# ACS_Temperature_Sensor.net
KiCad netlist of a schematic drawn in EasyEDA Pro
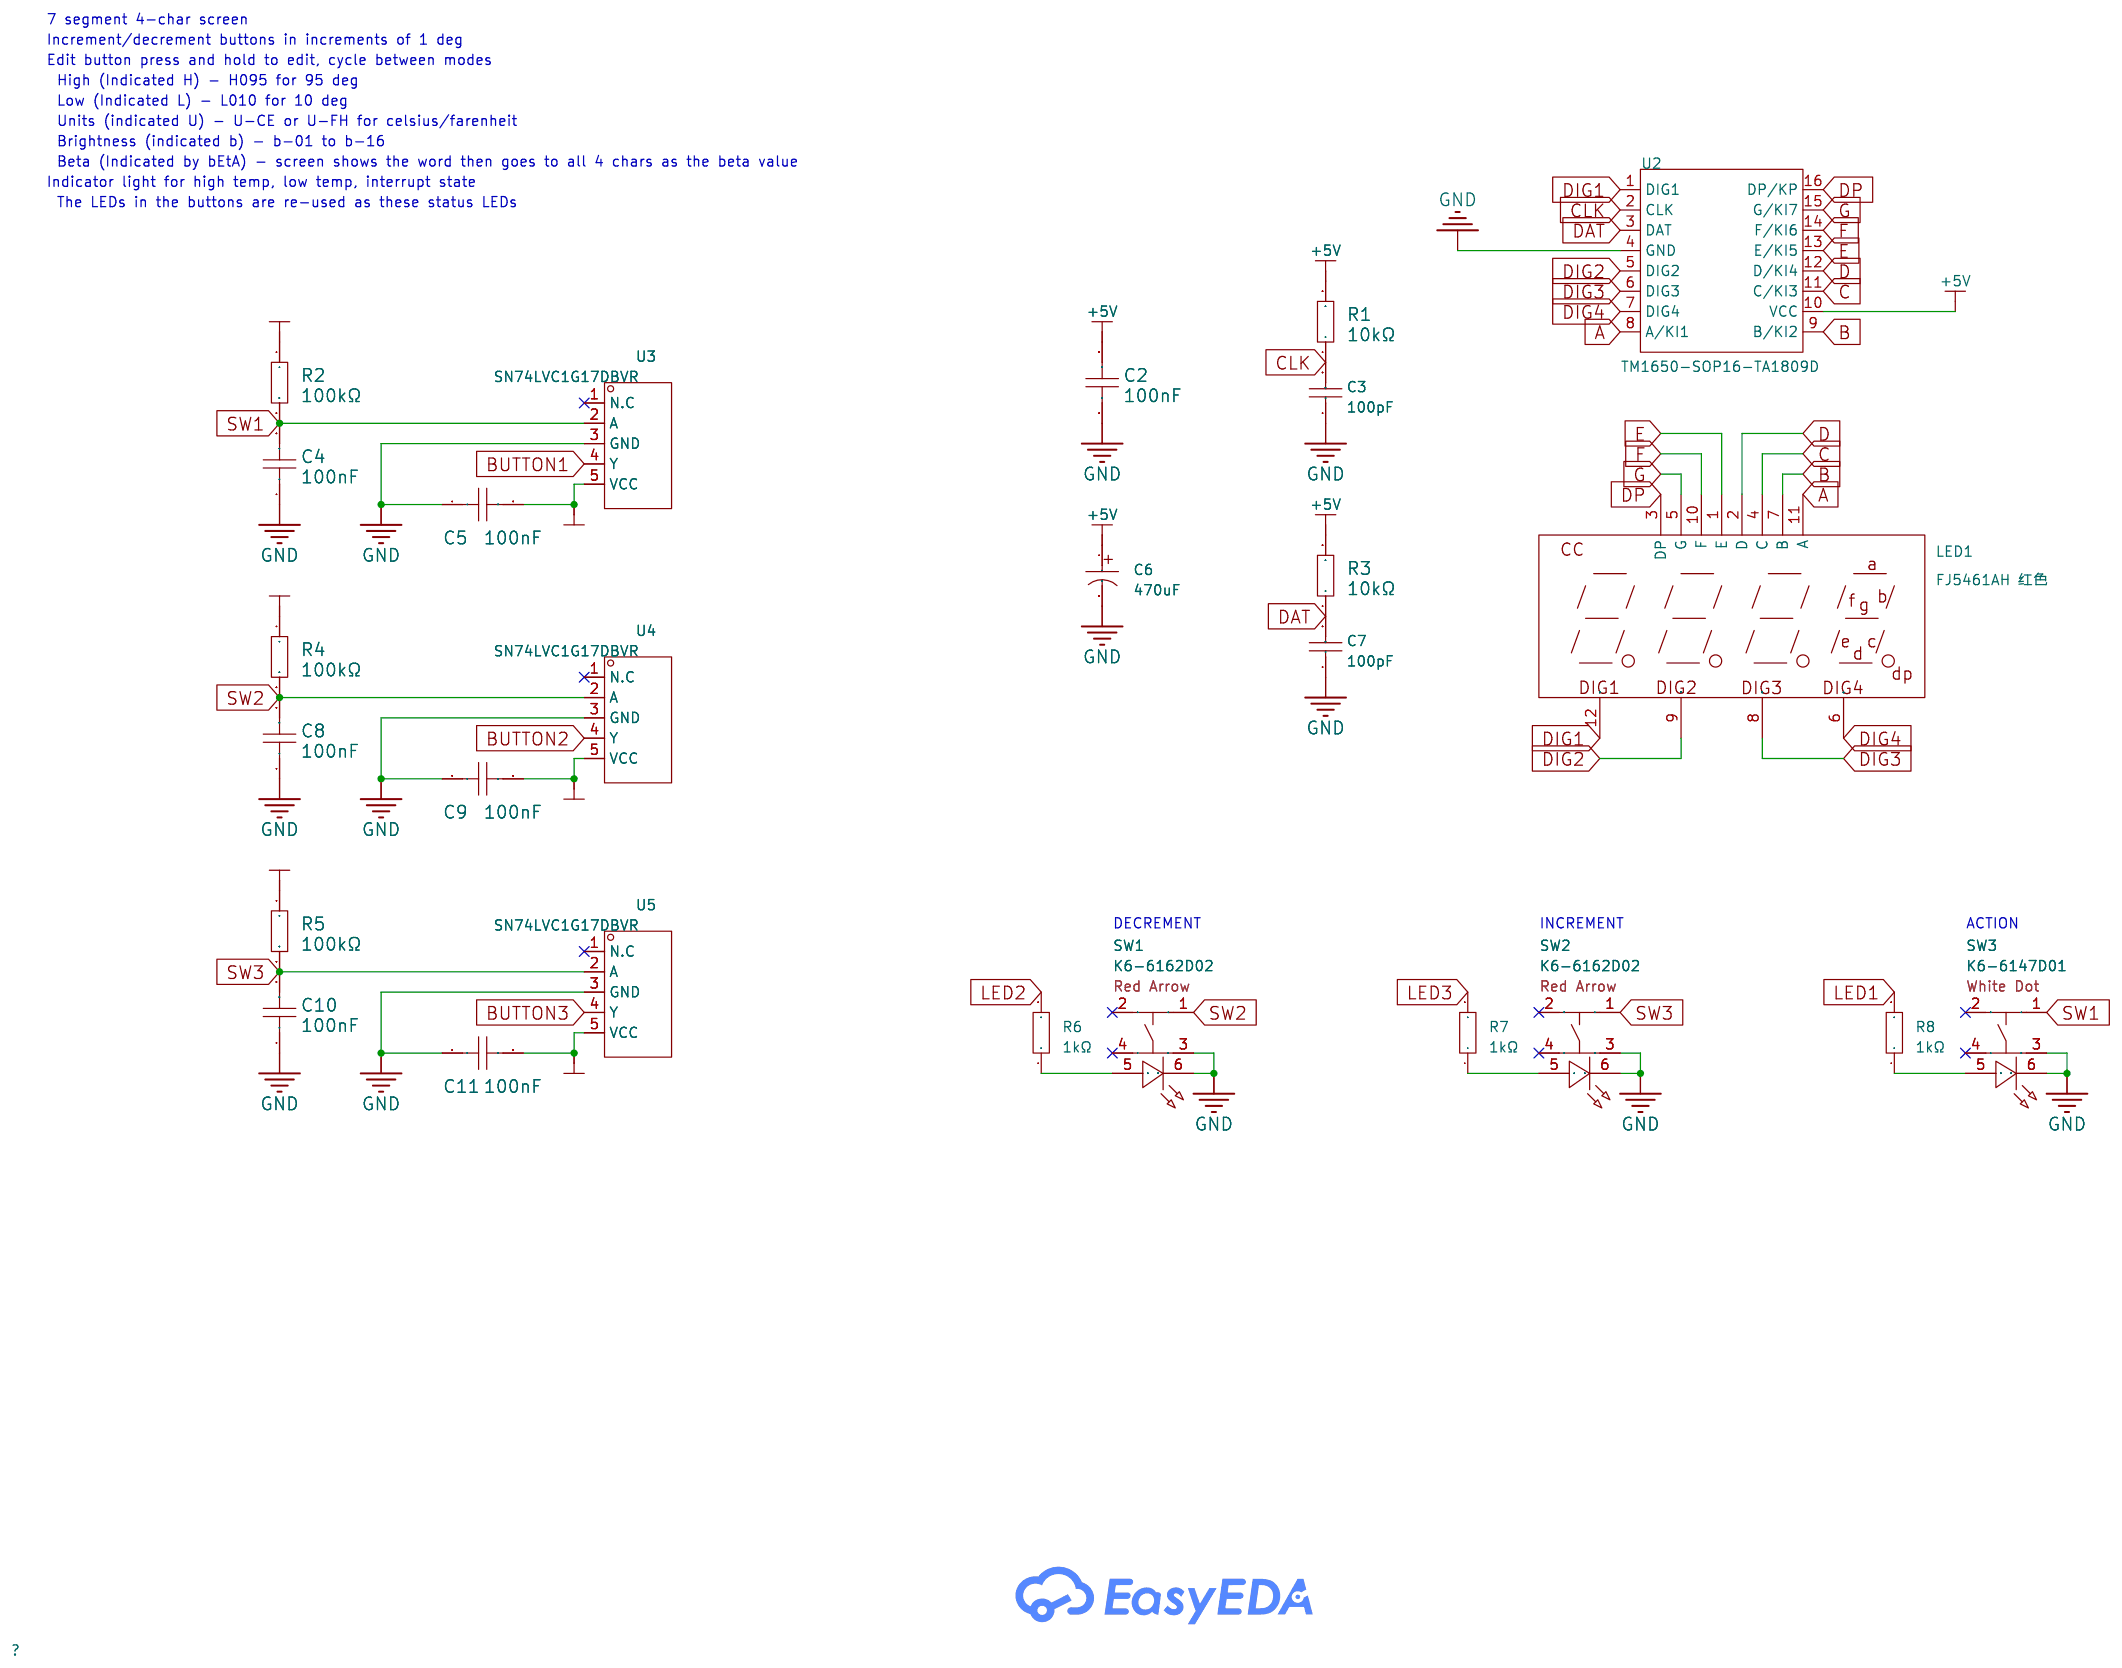
[diagram p0: User Interface]
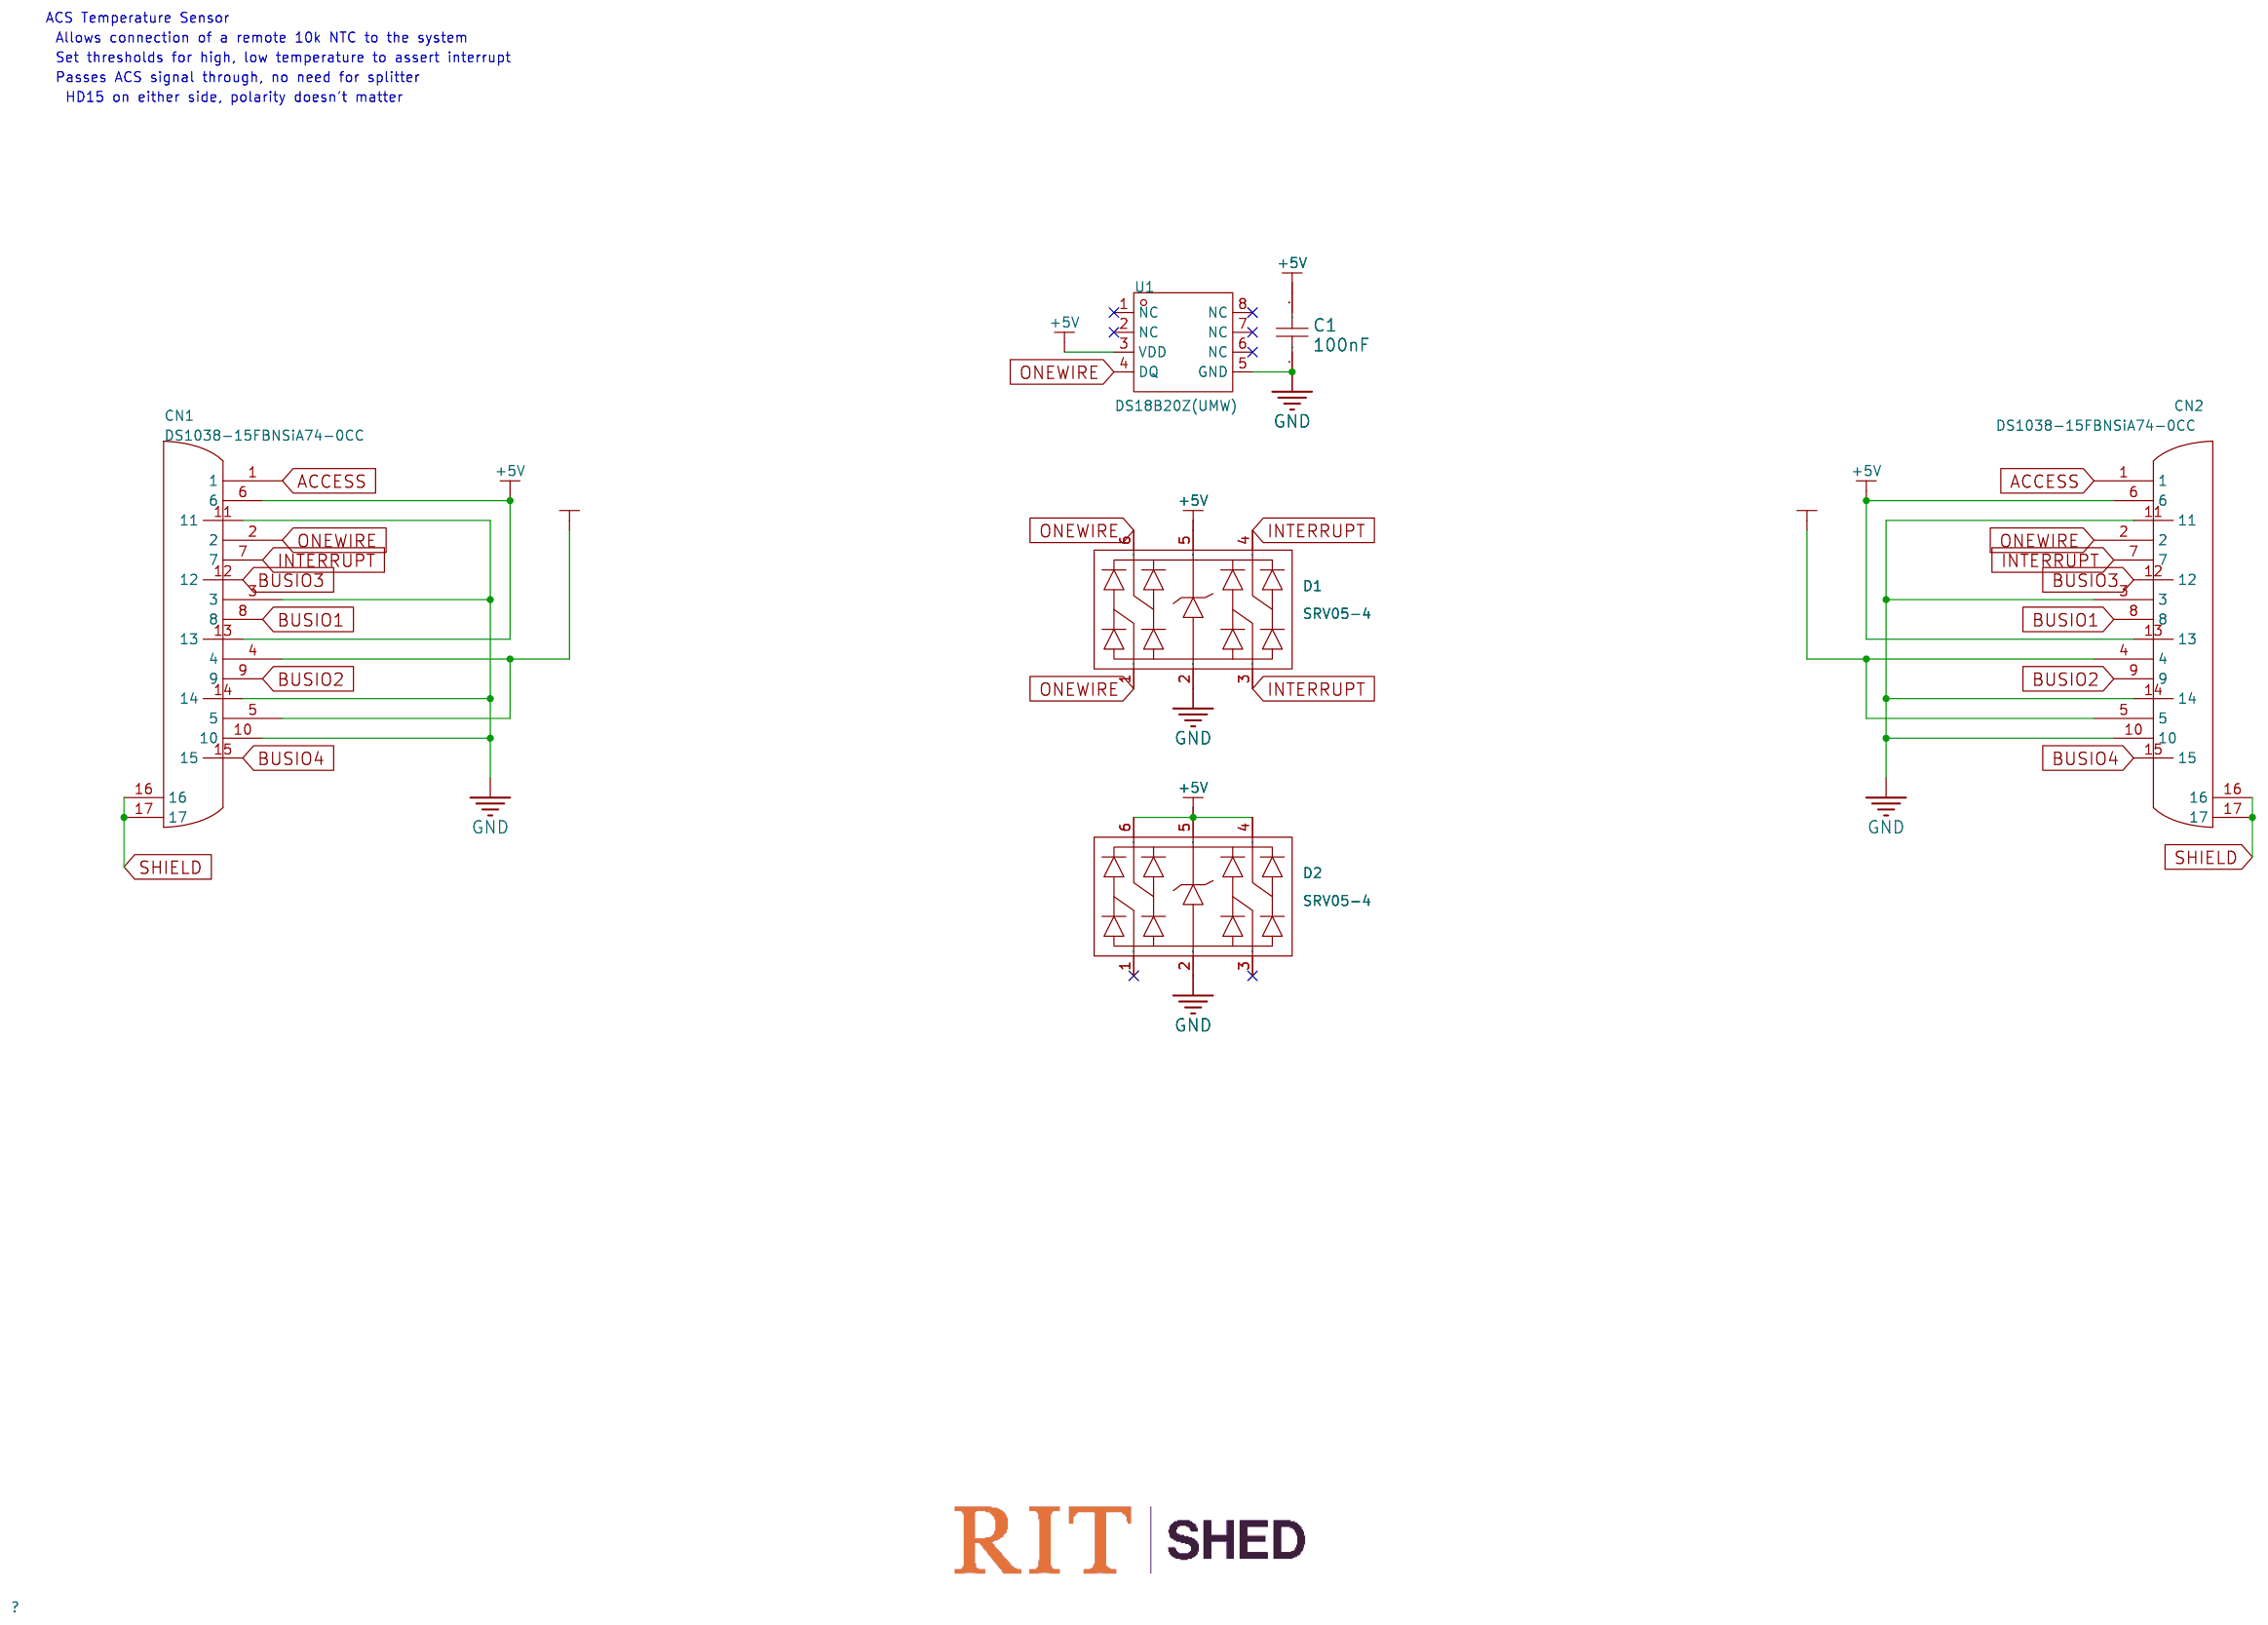
[diagram p1: ACS Interface]
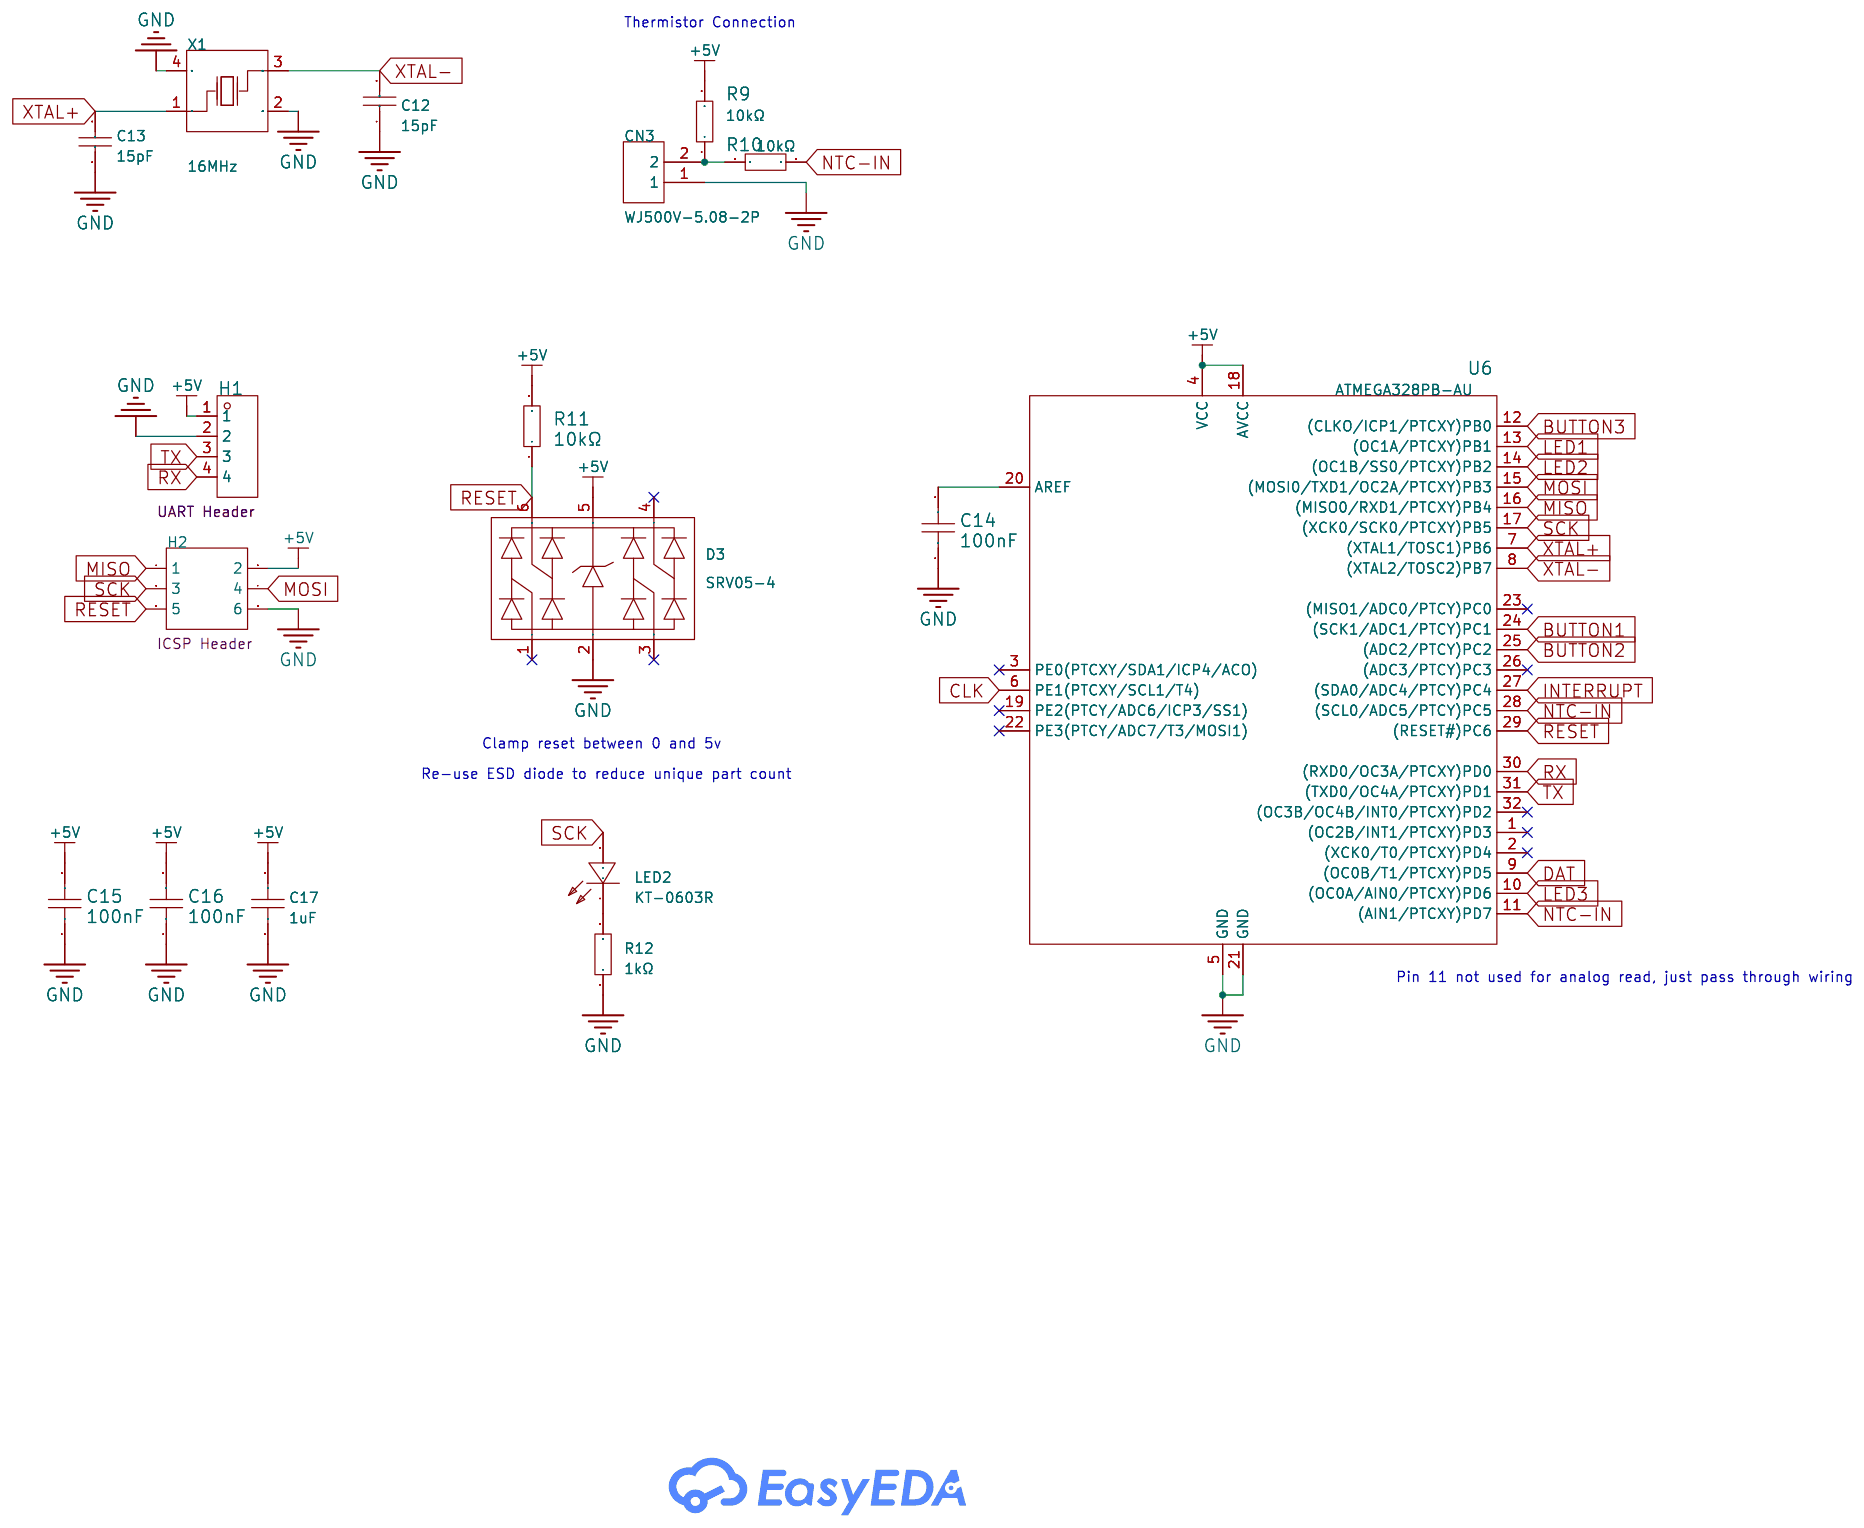
[diagram p2: Microcontroller]

(export (version "E")
  (design (tool "Eeschema 10.0.6"))
  (components
    (comp (ref "C2")
      (value "100nF")
      (footprint "easyedapro:C0603")
      (description "Capacitance:100nF Tolerance:±10% Tolerance:±10% Voltage Rating:50V Temperature Coefficient:X7R")
      (fields
        (field (name "Manufacturer Part") "CC0603KRX7R9BB104")
        (field (name "Manufacturer") "YAGEO(国巨)")
      )
      (libsource (lib "easyedapro") (part "CC0603KRX7R9BB104"))
    )
    (comp (ref "C3")
      (value "100pF")
      (footprint "easyedapro:C0603")
      (description "Capacitance:100pF Tolerance:±5% Tolerance:±5% Voltage Rating:50V Temperature Coefficient:C0G")
      (fields
        (field (name "Manufacturer Part") "CL10C101JB8NNNC")
        (field (name "Manufacturer") "SAMSUNG(三星)")
      )
      (libsource (lib "easyedapro") (part "CL10C101JB8NNNC"))
    )
    (comp (ref "C4")
      (value "100nF")
      (footprint "easyedapro:C0603")
      (description "Capacitance:100nF Tolerance:±10% Tolerance:±10% Voltage Rating:50V Temperature Coefficient:X7R")
      (fields
        (field (name "Manufacturer Part") "CC0603KRX7R9BB104")
        (field (name "Manufacturer") "YAGEO(国巨)")
      )
      (libsource (lib "easyedapro") (part "CC0603KRX7R9BB104"))
    )
    (comp (ref "C5")
      (value "100nF")
      (footprint "easyedapro:C0603")
      (description "Capacitance:100nF Tolerance:±10% Tolerance:±10% Voltage Rating:50V Temperature Coefficient:X7R")
      (fields
        (field (name "Manufacturer Part") "CC0603KRX7R9BB104")
        (field (name "Manufacturer") "YAGEO(国巨)")
      )
      (libsource (lib "easyedapro") (part "CC0603KRX7R9BB104"))
    )
    (comp (ref "C6")
      (value "470uF")
      (footprint "easyedapro:CAP-TH_BD8.0-P3.50-D0.6-FD")
      (fields
        (field (name "Manufacturer Part") "ZF477M016F07RR0VH4FPV")
        (field (name "Manufacturer") "Chengx(承兴)")
      )
      (libsource (lib "easyedapro") (part "470uF 16V 8*7Black high frequency"))
    )
    (comp (ref "C7")
      (value "100pF")
      (footprint "easyedapro:C0603")
      (description "Capacitance:100pF Tolerance:±5% Tolerance:±5% Voltage Rating:50V Temperature Coefficient:C0G")
      (fields
        (field (name "Manufacturer Part") "CL10C101JB8NNNC")
        (field (name "Manufacturer") "SAMSUNG(三星)")
      )
      (libsource (lib "easyedapro") (part "CL10C101JB8NNNC"))
    )
    (comp (ref "C8")
      (value "100nF")
      (footprint "easyedapro:C0603")
      (description "Capacitance:100nF Tolerance:±10% Tolerance:±10% Voltage Rating:50V Temperature Coefficient:X7R")
      (fields
        (field (name "Manufacturer Part") "CC0603KRX7R9BB104")
        (field (name "Manufacturer") "YAGEO(国巨)")
      )
      (libsource (lib "easyedapro") (part "CC0603KRX7R9BB104"))
    )
    (comp (ref "C9")
      (value "100nF")
      (footprint "easyedapro:C0603")
      (description "Capacitance:100nF Tolerance:±10% Tolerance:±10% Voltage Rating:50V Temperature Coefficient:X7R")
      (fields
        (field (name "Manufacturer Part") "CC0603KRX7R9BB104")
        (field (name "Manufacturer") "YAGEO(国巨)")
      )
      (libsource (lib "easyedapro") (part "CC0603KRX7R9BB104"))
    )
    (comp (ref "C10")
      (value "100nF")
      (footprint "easyedapro:C0603")
      (description "Capacitance:100nF Tolerance:±10% Tolerance:±10% Voltage Rating:50V Temperature Coefficient:X7R")
      (fields
        (field (name "Manufacturer Part") "CC0603KRX7R9BB104")
        (field (name "Manufacturer") "YAGEO(国巨)")
      )
      (libsource (lib "easyedapro") (part "CC0603KRX7R9BB104"))
    )
    (comp (ref "C11")
      (value "100nF")
      (footprint "easyedapro:C0603")
      (description "Capacitance:100nF Tolerance:±10% Tolerance:±10% Voltage Rating:50V Temperature Coefficient:X7R")
      (fields
        (field (name "Manufacturer Part") "CC0603KRX7R9BB104")
        (field (name "Manufacturer") "YAGEO(国巨)")
      )
      (libsource (lib "easyedapro") (part "CC0603KRX7R9BB104"))
    )
    (comp (ref "LED1")
      (value "FJ5461AH 红色")
      (footprint "easyedapro:LED-SEG-TH_FJ5461AH")
      (fields (field (name "Manufacturer") "志浩"))
      (libsource (lib "easyedapro") (part "FJ5461AH red"))
    )
    (comp (ref "R1")
      (value "10kΩ")
      (footprint "easyedapro:R0603")
      (fields
        (field (name "Manufacturer Part") "0603WAF1002T5E")
        (field (name "Manufacturer") "UNI-ROYAL(厚声)")
      )
      (libsource (lib "easyedapro") (part "0603WAF1002T5E"))
    )
    (comp (ref "R2")
      (value "100kΩ")
      (footprint "easyedapro:R0603")
      (fields
        (field (name "Manufacturer Part") "0603WAF1003T5E")
        (field (name "Manufacturer") "UNI-ROYAL(厚声)")
      )
      (libsource (lib "easyedapro") (part "0603WAF1003T5E"))
    )
    (comp (ref "R3")
      (value "10kΩ")
      (footprint "easyedapro:R0603")
      (fields
        (field (name "Manufacturer Part") "0603WAF1002T5E")
        (field (name "Manufacturer") "UNI-ROYAL(厚声)")
      )
      (libsource (lib "easyedapro") (part "0603WAF1002T5E"))
    )
    (comp (ref "R4")
      (value "100kΩ")
      (footprint "easyedapro:R0603")
      (fields
        (field (name "Manufacturer Part") "0603WAF1003T5E")
        (field (name "Manufacturer") "UNI-ROYAL(厚声)")
      )
      (libsource (lib "easyedapro") (part "0603WAF1003T5E"))
    )
    (comp (ref "R5")
      (value "100kΩ")
      (footprint "easyedapro:R0603")
      (fields
        (field (name "Manufacturer Part") "0603WAF1003T5E")
        (field (name "Manufacturer") "UNI-ROYAL(厚声)")
      )
      (libsource (lib "easyedapro") (part "0603WAF1003T5E"))
    )
    (comp (ref "R6")
      (value "1kΩ")
      (footprint "easyedapro:R0603")
      (fields
        (field (name "Manufacturer Part") "0603WAF1001T5E")
        (field (name "Manufacturer") "UNI-ROYAL(厚声)")
      )
      (libsource (lib "easyedapro") (part "0603WAF1001T5E"))
    )
    (comp (ref "R7")
      (value "1kΩ")
      (footprint "easyedapro:R0603")
      (fields
        (field (name "Manufacturer Part") "0603WAF1001T5E")
        (field (name "Manufacturer") "UNI-ROYAL(厚声)")
      )
      (libsource (lib "easyedapro") (part "0603WAF1001T5E"))
    )
    (comp (ref "R8")
      (value "1kΩ")
      (footprint "easyedapro:R0603")
      (fields
        (field (name "Manufacturer Part") "0603WAF1001T5E")
        (field (name "Manufacturer") "UNI-ROYAL(厚声)")
      )
      (libsource (lib "easyedapro") (part "0603WAF1001T5E"))
    )
    (comp (ref "SW1")
      (value "K6-6162D02")
      (footprint "easyedapro:SW-TH_K6-6162D04")
      (fields (field (name "Manufacturer") "韩国韩荣") (field (name "Note") "Red Arrow"))
      (libsource (lib "easyedapro") (part "K6-6162D02"))
    )
    (comp (ref "SW2")
      (value "K6-6162D02")
      (footprint "easyedapro:SW-TH_K6-6162D04")
      (fields (field (name "Manufacturer") "韩国韩荣") (field (name "Note") "Red Arrow"))
      (libsource (lib "easyedapro") (part "K6-6162D02"))
    )
    (comp (ref "SW3")
      (value "K6-6147D01")
      (footprint "easyedapro:SW-TH_K6-6162D04")
      (fields (field (name "Manufacturer") "韩国韩荣") (field (name "Note") "White Dot"))
      (libsource (lib "easyedapro") (part "K6-6147D01"))
    )
    (comp (ref "U2")
      (value "TM1650-SOP16-TA1809D")
      (footprint "easyedapro:SOP-16_L9.9-W3.9-P1.27-LS6.0-BL")
      (fields (field (name "Manufacturer") "TM(天微)"))
      (libsource (lib "easyedapro") (part "TM1650-SOP16-TA1809D"))
    )
    (comp (ref "U3")
      (value "SN74LVC1G17DBVR")
      (footprint "easyedapro:SOT-23-5_L3.0-W1.7-P0.95-LS2.8-BR")
      (fields (field (name "Manufacturer") "TI(德州仪器)"))
      (libsource (lib "easyedapro") (part "SN74LVC1G17DBVR"))
    )
    (comp (ref "U4")
      (value "SN74LVC1G17DBVR")
      (footprint "easyedapro:SOT-23-5_L3.0-W1.7-P0.95-LS2.8-BR")
      (fields (field (name "Manufacturer") "TI(德州仪器)"))
      (libsource (lib "easyedapro") (part "SN74LVC1G17DBVR"))
    )
    (comp (ref "U5")
      (value "SN74LVC1G17DBVR")
      (footprint "easyedapro:SOT-23-5_L3.0-W1.7-P0.95-LS2.8-BR")
      (fields (field (name "Manufacturer") "TI(德州仪器)"))
      (libsource (lib "easyedapro") (part "SN74LVC1G17DBVR"))
    )
    (comp (ref "C1")
      (value "100nF")
      (fields
        (field (name "Manufacturer Part") "CC0603KRX7R9BB104")
        (field (name "Manufacturer") "YAGEO(国巨)")
      )
      (libsource (lib "easyedapro") (part "CC0603KRX7R9BB104"))
    )
    (comp (ref "CN1")
      (value "DS1038-15FBNSiA74-0CC")
      (footprint "easyedapro:DSUB-TH_DS1038-15FBNSIA74-0CC")
      (fields (field (name "Manufacturer") "CONNFLY"))
      (libsource (lib "easyedapro") (part "DS1038-15FBNSIA74-0CC"))
    )
    (comp (ref "CN2")
      (value "DS1038-15FBNSiA74-0CC")
      (footprint "easyedapro:DSUB-TH_DS1038-15FBNSIA74-0CC")
      (fields (field (name "Manufacturer") "CONNFLY"))
      (libsource (lib "easyedapro") (part "DS1038-15FBNSIA74-0CC"))
    )
    (comp (ref "D1")
      (value "SRV05-4")
      (footprint "easyedapro:SOT-23-6_L2.9-W1.6-P0.95-LS2.8-BL")
      (fields (field (name "Manufacturer") "TECH PUBLIC(台舟)"))
      (libsource (lib "easyedapro") (part "SRV05-4_C558418"))
    )
    (comp (ref "D2")
      (value "SRV05-4")
      (footprint "easyedapro:SOT-23-6_L2.9-W1.6-P0.95-LS2.8-BL")
      (fields (field (name "Manufacturer") "TECH PUBLIC(台舟)"))
      (libsource (lib "easyedapro") (part "SRV05-4_C558418"))
    )
    (comp (ref "U1")
      (value "DS18B20Z(UMW)")
      (footprint "easyedapro:SOP-8_L4.9-W3.9-P1.27-LS6.0-BL")
      (fields (field (name "Manufacturer") "UMW(友台半导体)"))
      (libsource (lib "easyedapro") (part "DS18B20Z"))
    )
    (comp (ref "C12")
      (value "15pF")
      (footprint "easyedapro:C0603")
      (description "Capacitance:15pF Tolerance:±5% Tolerance:±5% Voltage Rating:50V Temperature Coefficient:C0G")
      (fields
        (field (name "Manufacturer Part") "CL10C150JB8NNNC")
        (field (name "Manufacturer") "SAMSUNG(三星)")
      )
      (libsource (lib "easyedapro") (part "CL10C150JB8NNNC"))
    )
    (comp (ref "C13")
      (value "15pF")
      (footprint "easyedapro:C0603")
      (description "Capacitance:15pF Tolerance:±5% Tolerance:±5% Voltage Rating:50V Temperature Coefficient:C0G")
      (fields
        (field (name "Manufacturer Part") "CL10C150JB8NNNC")
        (field (name "Manufacturer") "SAMSUNG(三星)")
      )
      (libsource (lib "easyedapro") (part "CL10C150JB8NNNC"))
    )
    (comp (ref "C14")
      (value "100nF")
      (fields
        (field (name "Manufacturer Part") "CC0603KRX7R9BB104")
        (field (name "Manufacturer") "YAGEO(国巨)")
      )
      (libsource (lib "easyedapro") (part "CC0603KRX7R9BB104"))
    )
    (comp (ref "C15")
      (value "100nF")
      (fields
        (field (name "Manufacturer Part") "CC0603KRX7R9BB104")
        (field (name "Manufacturer") "YAGEO(国巨)")
      )
      (libsource (lib "easyedapro") (part "CC0603KRX7R9BB104"))
    )
    (comp (ref "C16")
      (value "100nF")
      (fields
        (field (name "Manufacturer Part") "CC0603KRX7R9BB104")
        (field (name "Manufacturer") "YAGEO(国巨)")
      )
      (libsource (lib "easyedapro") (part "CC0603KRX7R9BB104"))
    )
    (comp (ref "C17")
      (value "1uF")
      (footprint "easyedapro:C0603")
      (description "Capacitance:1uF Tolerance:±10% Tolerance:±10% Voltage Rating:50V Temperature Coefficient:X5R")
      (fields
        (field (name "Manufacturer Part") "CL10A105KB8NNNC")
        (field (name "Manufacturer") "SAMSUNG(三星)")
      )
      (libsource (lib "easyedapro") (part "CL10A105KB8NNNC"))
    )
    (comp (ref "CN3")
      (value "WJ500V-5.08-2P")
      (footprint "easyedapro:CONN-TH_2P-P5.00_WJ500V-5.08-2P")
      (fields (field (name "Manufacturer") "KANGNEX(康奈克斯电气)"))
      (libsource (lib "easyedapro") (part "WJ500V-5.08-2P-14-00A"))
    )
    (comp (ref "D3")
      (value "SRV05-4")
      (footprint "easyedapro:SOT-23-6_L2.9-W1.6-P0.95-LS2.8-BL")
      (fields (field (name "Manufacturer") "TECH PUBLIC(台舟)"))
      (libsource (lib "easyedapro") (part "SRV05-4_C558418"))
    )
    (comp (ref "H1")
      (value "~")
      (footprint "easyedapro:HDR-TH_4P-P2.54-V-F")
      (description "UART Header")
      (libsource (lib "easyedapro") (part "2.54-1*4P母"))
    )
    (comp (ref "H2")
      (value "~")
      (footprint "easyedapro:HDR-TH_6P-P2.54-V-F-R2-C3-S2.54")
      (description "ICSP Header")
      (libsource (lib "easyedapro") (part "HDR-F-2.54_2x3"))
    )
    (comp (ref "LED2")
      (value "KT-0603R")
      (footprint "easyedapro:LED0603-RD")
      (fields (field (name "Manufacturer") "KENTO"))
      (libsource (lib "easyedapro") (part "KT-0603R"))
    )
    (comp (ref "R9")
      (value "10kΩ")
      (footprint "easyedapro:R0603")
      (fields
        (field (name "Manufacturer Part") "0603WAF1002T5E")
        (field (name "Manufacturer") "UNI-ROYAL(厚声)")
      )
      (libsource (lib "easyedapro") (part "0603WAF1002T5E"))
    )
    (comp (ref "R10")
      (value "10kΩ")
      (footprint "easyedapro:R0603")
      (fields
        (field (name "Manufacturer Part") "0603WAF1002T5E")
        (field (name "Manufacturer") "UNI-ROYAL(厚声)")
      )
      (libsource (lib "easyedapro") (part "0603WAF1002T5E"))
    )
    (comp (ref "R11")
      (value "10kΩ")
      (footprint "easyedapro:R0603")
      (fields
        (field (name "Manufacturer Part") "0603WAF1002T5E")
        (field (name "Manufacturer") "UNI-ROYAL(厚声)")
      )
      (libsource (lib "easyedapro") (part "0603WAF1002T5E"))
    )
    (comp (ref "R12")
      (value "1kΩ")
      (footprint "easyedapro:R0603")
      (fields
        (field (name "Manufacturer Part") "0603WAF1001T5E")
        (field (name "Manufacturer") "UNI-ROYAL(厚声)")
      )
      (libsource (lib "easyedapro") (part "0603WAF1001T5E"))
    )
    (comp (ref "U6")
      (value "ATMEGA328PB-AU")
      (footprint "easyedapro:TQFP-32_L7.0-W7.0-P0.80-LS9.0-BL")
      (fields (field (name "Manufacturer") "MICROCHIP(美国微芯)"))
      (libsource (lib "easyedapro") (part "ATMEGA328PB-AU"))
    )
    (comp (ref "X1")
      (value "16MHz")
      (footprint "easyedapro:OSC-SMD_4P-L3.2-W2.5-BL")
      (fields (field (name "Manufacturer Part") "X322516MLB4SI") (field (name "Manufacturer") "YXC(扬兴晶振)"))
      (libsource (lib "easyedapro") (part "X322516MLB4SI"))
    )
  )
  (nets
    (net (code "1") (name "+5V") (class "Default")
      (node (ref "C1") (pin "2") (pinfunction "2_2") (pintype "input"))
      (node (ref "C11") (pin "2") (pinfunction "2_2") (pintype "unspecified"))
      (node (ref "C15") (pin "2") (pinfunction "2_2") (pintype "input"))
      (node (ref "C16") (pin "2") (pinfunction "2_2") (pintype "input"))
      (node (ref "C17") (pin "2") (pinfunction "2_2") (pintype "unspecified"))
      (node (ref "C2") (pin "2") (pinfunction "2_2") (pintype "unspecified"))
      (node (ref "C5") (pin "2") (pinfunction "2_2") (pintype "unspecified"))
      (node (ref "C6") (pin "1") (pinfunction "1_1") (pintype "input"))
      (node (ref "C9") (pin "2") (pinfunction "2_2") (pintype "unspecified"))
      (node (ref "CN1") (pin "13") (pinfunction "13_13") (pintype "unspecified"))
      (node (ref "CN1") (pin "6") (pinfunction "6_6") (pintype "unspecified"))
      (node (ref "CN2") (pin "13") (pinfunction "13_13") (pintype "unspecified"))
      (node (ref "CN2") (pin "6") (pinfunction "6_6") (pintype "unspecified"))
      (node (ref "D1") (pin "5") (pinfunction "5_5") (pintype "unspecified"))
      (node (ref "D2") (pin "4") (pinfunction "4_4") (pintype "unspecified"))
      (node (ref "D2") (pin "5") (pinfunction "5_5") (pintype "unspecified"))
      (node (ref "D2") (pin "6") (pinfunction "6_6") (pintype "unspecified"))
      (node (ref "D3") (pin "5") (pinfunction "5_5") (pintype "unspecified"))
      (node (ref "H1") (pin "1") (pinfunction "1_1") (pintype "input"))
      (node (ref "H2") (pin "2") (pinfunction "2_2") (pintype "input"))
      (node (ref "R1") (pin "2") (pinfunction "2_2") (pintype "input"))
      (node (ref "R11") (pin "2") (pinfunction "2_2") (pintype "input"))
      (node (ref "R2") (pin "1") (pinfunction "1_1") (pintype "input"))
      (node (ref "R3") (pin "2") (pinfunction "2_2") (pintype "input"))
      (node (ref "R4") (pin "1") (pinfunction "1_1") (pintype "input"))
      (node (ref "R5") (pin "1") (pinfunction "1_1") (pintype "input"))
      (node (ref "R9") (pin "2") (pinfunction "2_2") (pintype "input"))
      (node (ref "U1") (pin "3") (pinfunction "VDD_3") (pintype "unspecified"))
      (node (ref "U2") (pin "10") (pinfunction "VCC_10") (pintype "unspecified"))
      (node (ref "U3") (pin "5") (pinfunction "VCC_5") (pintype "unspecified"))
      (node (ref "U4") (pin "5") (pinfunction "VCC_5") (pintype "unspecified"))
      (node (ref "U5") (pin "5") (pinfunction "VCC_5") (pintype "unspecified"))
      (node (ref "U6") (pin "18") (pinfunction "AVCC_18") (pintype "bidirectional"))
      (node (ref "U6") (pin "4") (pinfunction "VCC_4") (pintype "bidirectional"))
    )
    (net (code "2") (name "+12V-BUS") (class "Default")
      (node (ref "CN1") (pin "4") (pinfunction "4_4") (pintype "unspecified"))
      (node (ref "CN1") (pin "5") (pinfunction "5_5") (pintype "unspecified"))
      (node (ref "CN2") (pin "4") (pinfunction "4_4") (pintype "unspecified"))
      (node (ref "CN2") (pin "5") (pinfunction "5_5") (pintype "unspecified"))
    )
    (net (code "3") (name "A") (class "Default")
      (node (ref "LED1") (pin "11") (pinfunction "A_11") (pintype "input"))
      (node (ref "U2") (pin "8") (pinfunction "A/KI1_8") (pintype "unspecified"))
    )
    (net (code "4") (name "ACCESS") (class "Default")
      (node (ref "CN1") (pin "1") (pinfunction "1_1") (pintype "unspecified"))
      (node (ref "CN2") (pin "1") (pinfunction "1_1") (pintype "unspecified"))
    )
    (net (code "5") (name "B") (class "Default")
      (node (ref "LED1") (pin "7") (pinfunction "B_7") (pintype "input"))
      (node (ref "U2") (pin "9") (pinfunction "B/KI2_9") (pintype "unspecified"))
    )
    (net (code "6") (name "BUSIO1") (class "Default")
      (node (ref "CN1") (pin "8") (pinfunction "8_8") (pintype "unspecified"))
      (node (ref "CN2") (pin "8") (pinfunction "8_8") (pintype "unspecified"))
    )
    (net (code "7") (name "BUSIO2") (class "Default")
      (node (ref "CN1") (pin "9") (pinfunction "9_9") (pintype "unspecified"))
      (node (ref "CN2") (pin "9") (pinfunction "9_9") (pintype "unspecified"))
    )
    (net (code "8") (name "BUSIO3") (class "Default")
      (node (ref "CN1") (pin "12") (pinfunction "12_12") (pintype "unspecified"))
      (node (ref "CN2") (pin "12") (pinfunction "12_12") (pintype "unspecified"))
    )
    (net (code "9") (name "BUSIO4") (class "Default")
      (node (ref "CN1") (pin "15") (pinfunction "15_15") (pintype "unspecified"))
      (node (ref "CN2") (pin "15") (pinfunction "15_15") (pintype "unspecified"))
    )
    (net (code "10") (name "BUTTON1") (class "Default")
      (node (ref "U3") (pin "4") (pinfunction "Y_4") (pintype "unspecified"))
      (node (ref "U6") (pin "24") (pinfunction "(SCK1/ADC1/PTCY)PC1_24") (pintype "bidirectional"))
    )
    (net (code "11") (name "BUTTON2") (class "Default")
      (node (ref "U4") (pin "4") (pinfunction "Y_4") (pintype "unspecified"))
      (node (ref "U6") (pin "25") (pinfunction "(ADC2/PTCY)PC2_25") (pintype "bidirectional"))
    )
    (net (code "12") (name "BUTTON3") (class "Default")
      (node (ref "U5") (pin "4") (pinfunction "Y_4") (pintype "unspecified"))
      (node (ref "U6") (pin "12") (pinfunction "(CLKO/ICP1/PTCXY)PB0_12") (pintype "bidirectional"))
    )
    (net (code "13") (name "C") (class "Default")
      (node (ref "LED1") (pin "4") (pinfunction "C_4") (pintype "input"))
      (node (ref "U2") (pin "11") (pinfunction "C/KI3_11") (pintype "unspecified"))
    )
    (net (code "14") (name "CLK") (class "Default")
      (node (ref "C3") (pin "2") (pinfunction "2_2") (pintype "input"))
      (node (ref "R1") (pin "1") (pinfunction "1_1") (pintype "input"))
      (node (ref "U2") (pin "2") (pinfunction "CLK_2") (pintype "unspecified"))
      (node (ref "U6") (pin "6") (pinfunction "PE1(PTCXY/SCL1/T4)_6") (pintype "bidirectional"))
    )
    (net (code "15") (name "D") (class "Default")
      (node (ref "LED1") (pin "2") (pinfunction "D_2") (pintype "input"))
      (node (ref "U2") (pin "12") (pinfunction "D/KI4_12") (pintype "unspecified"))
    )
    (net (code "16") (name "DAT") (class "Default")
      (node (ref "C7") (pin "2") (pinfunction "2_2") (pintype "input"))
      (node (ref "R3") (pin "1") (pinfunction "1_1") (pintype "input"))
      (node (ref "U2") (pin "3") (pinfunction "DAT_3") (pintype "unspecified"))
      (node (ref "U6") (pin "9") (pinfunction "(OC0B/T1/PTCXY)PD5_9") (pintype "bidirectional"))
    )
    (net (code "17") (name "DIG1") (class "Default")
      (node (ref "LED1") (pin "12") (pinfunction "DIG1_12") (pintype "input"))
      (node (ref "U2") (pin "1") (pinfunction "DIG1_1") (pintype "unspecified"))
    )
    (net (code "18") (name "DIG2") (class "Default")
      (node (ref "LED1") (pin "9") (pinfunction "DIG2_9") (pintype "input"))
      (node (ref "U2") (pin "5") (pinfunction "DIG2_5") (pintype "unspecified"))
    )
    (net (code "19") (name "DIG3") (class "Default")
      (node (ref "LED1") (pin "8") (pinfunction "DIG3_8") (pintype "input"))
      (node (ref "U2") (pin "6") (pinfunction "DIG3_6") (pintype "unspecified"))
    )
    (net (code "20") (name "DIG4") (class "Default")
      (node (ref "LED1") (pin "6") (pinfunction "DIG4_6") (pintype "input"))
      (node (ref "U2") (pin "7") (pinfunction "DIG4_7") (pintype "unspecified"))
    )
    (net (code "21") (name "DP") (class "Default")
      (node (ref "LED1") (pin "3") (pinfunction "DP_3") (pintype "input"))
      (node (ref "U2") (pin "16") (pinfunction "DP/KP_16") (pintype "unspecified"))
    )
    (net (code "22") (name "E") (class "Default")
      (node (ref "LED1") (pin "1") (pinfunction "E_1") (pintype "input"))
      (node (ref "U2") (pin "13") (pinfunction "E/KI5_13") (pintype "unspecified"))
    )
    (net (code "23") (name "F") (class "Default")
      (node (ref "LED1") (pin "10") (pinfunction "F_10") (pintype "input"))
      (node (ref "U2") (pin "14") (pinfunction "F/KI6_14") (pintype "unspecified"))
    )
    (net (code "24") (name "G") (class "Default")
      (node (ref "LED1") (pin "5") (pinfunction "G_5") (pintype "input"))
      (node (ref "U2") (pin "15") (pinfunction "G/KI7_15") (pintype "unspecified"))
    )
    (net (code "25") (name "GND") (class "Default")
      (node (ref "C1") (pin "1") (pinfunction "1_1") (pintype "input"))
      (node (ref "C10") (pin "1") (pinfunction "1_1") (pintype "unspecified"))
      (node (ref "C11") (pin "1") (pinfunction "1_1") (pintype "unspecified"))
      (node (ref "C12") (pin "1") (pinfunction "1_1") (pintype "input"))
      (node (ref "C13") (pin "1") (pinfunction "1_1") (pintype "input"))
      (node (ref "C14") (pin "1") (pinfunction "1_1") (pintype "input"))
      (node (ref "C15") (pin "1") (pinfunction "1_1") (pintype "input"))
      (node (ref "C16") (pin "1") (pinfunction "1_1") (pintype "input"))
      (node (ref "C17") (pin "1") (pinfunction "1_1") (pintype "unspecified"))
      (node (ref "C2") (pin "1") (pinfunction "1_1") (pintype "unspecified"))
      (node (ref "C3") (pin "1") (pinfunction "1_1") (pintype "input"))
      (node (ref "C4") (pin "1") (pinfunction "1_1") (pintype "unspecified"))
      (node (ref "C5") (pin "1") (pinfunction "1_1") (pintype "unspecified"))
      (node (ref "C6") (pin "2") (pinfunction "2_2") (pintype "input"))
      (node (ref "C7") (pin "1") (pinfunction "1_1") (pintype "input"))
      (node (ref "C8") (pin "1") (pinfunction "1_1") (pintype "unspecified"))
      (node (ref "C9") (pin "1") (pinfunction "1_1") (pintype "unspecified"))
      (node (ref "CN1") (pin "10") (pinfunction "10_10") (pintype "unspecified"))
      (node (ref "CN1") (pin "11") (pinfunction "11_11") (pintype "unspecified"))
      (node (ref "CN1") (pin "14") (pinfunction "14_14") (pintype "unspecified"))
      (node (ref "CN1") (pin "3") (pinfunction "3_3") (pintype "unspecified"))
      (node (ref "CN2") (pin "10") (pinfunction "10_10") (pintype "unspecified"))
      (node (ref "CN2") (pin "11") (pinfunction "11_11") (pintype "unspecified"))
      (node (ref "CN2") (pin "14") (pinfunction "14_14") (pintype "unspecified"))
      (node (ref "CN2") (pin "3") (pinfunction "3_3") (pintype "unspecified"))
      (node (ref "CN3") (pin "1") (pinfunction "1_1") (pintype "unspecified"))
      (node (ref "D1") (pin "2") (pinfunction "2_2") (pintype "unspecified"))
      (node (ref "D2") (pin "2") (pinfunction "2_2") (pintype "unspecified"))
      (node (ref "D3") (pin "2") (pinfunction "2_2") (pintype "unspecified"))
      (node (ref "H1") (pin "2") (pinfunction "2_2") (pintype "input"))
      (node (ref "H2") (pin "6") (pinfunction "6_6") (pintype "input"))
      (node (ref "R12") (pin "1") (pinfunction "1_1") (pintype "input"))
      (node (ref "SW1") (pin "3") (pinfunction "3_3") (pintype "unspecified"))
      (node (ref "SW1") (pin "6") (pinfunction "6_6") (pintype "unspecified"))
      (node (ref "SW2") (pin "3") (pinfunction "3_3") (pintype "unspecified"))
      (node (ref "SW2") (pin "6") (pinfunction "6_6") (pintype "unspecified"))
      (node (ref "SW3") (pin "3") (pinfunction "3_3") (pintype "unspecified"))
      (node (ref "SW3") (pin "6") (pinfunction "6_6") (pintype "unspecified"))
      (node (ref "U1") (pin "5") (pinfunction "GND_5") (pintype "unspecified"))
      (node (ref "U2") (pin "4") (pinfunction "GND_4") (pintype "unspecified"))
      (node (ref "U3") (pin "3") (pinfunction "GND_3") (pintype "unspecified"))
      (node (ref "U4") (pin "3") (pinfunction "GND_3") (pintype "unspecified"))
      (node (ref "U5") (pin "3") (pinfunction "GND_3") (pintype "unspecified"))
      (node (ref "U6") (pin "21") (pinfunction "GND_21") (pintype "bidirectional"))
      (node (ref "U6") (pin "5") (pinfunction "GND_5") (pintype "bidirectional"))
      (node (ref "X1") (pin "2") (pinfunction "GND_2") (pintype "unspecified"))
      (node (ref "X1") (pin "4") (pinfunction "GND_4") (pintype "unspecified"))
    )
    (net (code "26") (name "INTERRUPT") (class "Default")
      (node (ref "CN1") (pin "7") (pinfunction "7_7") (pintype "unspecified"))
      (node (ref "CN2") (pin "7") (pinfunction "7_7") (pintype "unspecified"))
      (node (ref "D1") (pin "3") (pinfunction "3_3") (pintype "unspecified"))
      (node (ref "D1") (pin "4") (pinfunction "4_4") (pintype "unspecified"))
      (node (ref "U6") (pin "27") (pinfunction "(SDA0/ADC4/PTCY)PC4_27") (pintype "bidirectional"))
    )
    (net (code "27") (name "LED1") (class "Default")
      (node (ref "R8") (pin "2") (pinfunction "2_2") (pintype "input"))
      (node (ref "U6") (pin "13") (pinfunction "(OC1A/PTCXY)PB1_13") (pintype "bidirectional"))
    )
    (net (code "28") (name "LED2") (class "Default")
      (node (ref "R6") (pin "2") (pinfunction "2_2") (pintype "input"))
      (node (ref "U6") (pin "14") (pinfunction "(OC1B/SS0/PTCXY)PB2_14") (pintype "bidirectional"))
    )
    (net (code "29") (name "LED3") (class "Default")
      (node (ref "R7") (pin "2") (pinfunction "2_2") (pintype "input"))
      (node (ref "U6") (pin "10") (pinfunction "(OC0A/AIN0/PTCXY)PD6_10") (pintype "bidirectional"))
    )
    (net (code "30") (name "MISO") (class "Default")
      (node (ref "H2") (pin "1") (pinfunction "1_1") (pintype "input"))
      (node (ref "U6") (pin "16") (pinfunction "(MISO0/RXD1/PTCXY)PB4_16") (pintype "bidirectional"))
    )
    (net (code "31") (name "MOSI") (class "Default")
      (node (ref "H2") (pin "4") (pinfunction "4_4") (pintype "input"))
      (node (ref "U6") (pin "15") (pinfunction "(MOSI0/TXD1/OC2A/PTCXY)PB3_15") (pintype "bidirectional"))
    )
    (net (code "32") (name "NTC-IN") (class "Default")
      (node (ref "R10") (pin "1") (pinfunction "1_1") (pintype "input"))
      (node (ref "U6") (pin "11") (pinfunction "(AIN1/PTCXY)PD7_11") (pintype "bidirectional"))
      (node (ref "U6") (pin "28") (pinfunction "(SCL0/ADC5/PTCY)PC5_28") (pintype "bidirectional"))
    )
    (net (code "33") (name "Net-(CN3-Pad2)") (class "Default")
      (node (ref "CN3") (pin "2") (pinfunction "2_2") (pintype "unspecified"))
      (node (ref "R10") (pin "2") (pinfunction "2_2") (pintype "input"))
      (node (ref "R9") (pin "1") (pinfunction "1_1") (pintype "input"))
    )
    (net (code "34") (name "Net-(LED2-K)") (class "Default")
      (node (ref "LED2") (pin "1") (pinfunction "K_1") (pintype "unspecified"))
      (node (ref "R12") (pin "2") (pinfunction "2_2") (pintype "input"))
    )
    (net (code "35") (name "Net-(R6-Pad1)") (class "Default")
      (node (ref "R6") (pin "1") (pinfunction "1_1") (pintype "input"))
      (node (ref "SW1") (pin "5") (pinfunction "5_5") (pintype "unspecified"))
    )
    (net (code "36") (name "Net-(R7-Pad1)") (class "Default")
      (node (ref "R7") (pin "1") (pinfunction "1_1") (pintype "input"))
      (node (ref "SW2") (pin "5") (pinfunction "5_5") (pintype "unspecified"))
    )
    (net (code "37") (name "Net-(R8-Pad1)") (class "Default")
      (node (ref "R8") (pin "1") (pinfunction "1_1") (pintype "input"))
      (node (ref "SW3") (pin "5") (pinfunction "5_5") (pintype "unspecified"))
    )
    (net (code "38") (name "Net-(U6-AREF)") (class "Default")
      (node (ref "C14") (pin "2") (pinfunction "2_2") (pintype "input"))
      (node (ref "U6") (pin "20") (pinfunction "AREF_20") (pintype "bidirectional"))
    )
    (net (code "39") (name "ONEWIRE") (class "Default")
      (node (ref "CN1") (pin "2") (pinfunction "2_2") (pintype "unspecified"))
      (node (ref "CN2") (pin "2") (pinfunction "2_2") (pintype "unspecified"))
      (node (ref "D1") (pin "1") (pinfunction "1_1") (pintype "unspecified"))
      (node (ref "D1") (pin "6") (pinfunction "6_6") (pintype "unspecified"))
      (node (ref "U1") (pin "4") (pinfunction "DQ_4") (pintype "unspecified"))
    )
    (net (code "40") (name "RESET") (class "Default")
      (node (ref "D3") (pin "6") (pinfunction "6_6") (pintype "unspecified"))
      (node (ref "H2") (pin "5") (pinfunction "5_5") (pintype "input"))
      (node (ref "R11") (pin "1") (pinfunction "1_1") (pintype "input"))
      (node (ref "U6") (pin "29") (pinfunction "(RESET#)PC6_29") (pintype "bidirectional"))
    )
    (net (code "41") (name "RX") (class "Default")
      (node (ref "H1") (pin "4") (pinfunction "4_4") (pintype "input"))
      (node (ref "U6") (pin "30") (pinfunction "(RXD0/OC3A/PTCXY)PD0_30") (pintype "bidirectional"))
    )
    (net (code "42") (name "SCK") (class "Default")
      (node (ref "H2") (pin "3") (pinfunction "3_3") (pintype "input"))
      (node (ref "LED2") (pin "2") (pinfunction "A_2") (pintype "unspecified"))
      (node (ref "U6") (pin "17") (pinfunction "(XCK0/SCK0/PTCXY)PB5_17") (pintype "bidirectional"))
    )
    (net (code "43") (name "SHIELD") (class "Default")
      (node (ref "CN1") (pin "16") (pinfunction "16_16") (pintype "unspecified"))
      (node (ref "CN1") (pin "17") (pinfunction "17_17") (pintype "unspecified"))
      (node (ref "CN2") (pin "16") (pinfunction "16_16") (pintype "unspecified"))
      (node (ref "CN2") (pin "17") (pinfunction "17_17") (pintype "unspecified"))
    )
    (net (code "44") (name "SW1") (class "Default")
      (node (ref "C4") (pin "2") (pinfunction "2_2") (pintype "unspecified"))
      (node (ref "R2") (pin "2") (pinfunction "2_2") (pintype "input"))
      (node (ref "SW3") (pin "1") (pinfunction "1_1") (pintype "unspecified"))
      (node (ref "U3") (pin "2") (pinfunction "A_2") (pintype "unspecified"))
    )
    (net (code "45") (name "SW2") (class "Default")
      (node (ref "C8") (pin "2") (pinfunction "2_2") (pintype "unspecified"))
      (node (ref "R4") (pin "2") (pinfunction "2_2") (pintype "input"))
      (node (ref "SW1") (pin "1") (pinfunction "1_1") (pintype "unspecified"))
      (node (ref "U4") (pin "2") (pinfunction "A_2") (pintype "unspecified"))
    )
    (net (code "46") (name "SW3") (class "Default")
      (node (ref "C10") (pin "2") (pinfunction "2_2") (pintype "unspecified"))
      (node (ref "R5") (pin "2") (pinfunction "2_2") (pintype "input"))
      (node (ref "SW2") (pin "1") (pinfunction "1_1") (pintype "unspecified"))
      (node (ref "U5") (pin "2") (pinfunction "A_2") (pintype "unspecified"))
    )
    (net (code "47") (name "TX") (class "Default")
      (node (ref "H1") (pin "3") (pinfunction "3_3") (pintype "input"))
      (node (ref "U6") (pin "31") (pinfunction "(TXD0/OC4A/PTCXY)PD1_31") (pintype "bidirectional"))
    )
    (net (code "48") (name "XTAL+") (class "Default")
      (node (ref "C13") (pin "2") (pinfunction "2_2") (pintype "input"))
      (node (ref "U6") (pin "7") (pinfunction "(XTAL1/TOSC1)PB6_7") (pintype "bidirectional"))
      (node (ref "X1") (pin "1") (pinfunction "OSC1_1") (pintype "unspecified"))
    )
    (net (code "49") (name "XTAL-") (class "Default")
      (node (ref "C12") (pin "2") (pinfunction "2_2") (pintype "input"))
      (node (ref "U6") (pin "8") (pinfunction "(XTAL2/TOSC2)PB7_8") (pintype "bidirectional"))
      (node (ref "X1") (pin "3") (pinfunction "OSC2_3") (pintype "unspecified"))
    )
    (net (code "50") (name "unconnected-(D2-Pad1)") (class "Default")
      (node (ref "D2") (pin "1") (pinfunction "1_1") (pintype "unspecified+no_connect"))
    )
    (net (code "51") (name "unconnected-(D2-Pad3)") (class "Default")
      (node (ref "D2") (pin "3") (pinfunction "3_3") (pintype "unspecified+no_connect"))
    )
    (net (code "52") (name "unconnected-(D3-Pad1)") (class "Default")
      (node (ref "D3") (pin "1") (pinfunction "1_1") (pintype "unspecified+no_connect"))
    )
    (net (code "53") (name "unconnected-(D3-Pad3)") (class "Default")
      (node (ref "D3") (pin "3") (pinfunction "3_3") (pintype "unspecified+no_connect"))
    )
    (net (code "54") (name "unconnected-(D3-Pad4)") (class "Default")
      (node (ref "D3") (pin "4") (pinfunction "4_4") (pintype "unspecified+no_connect"))
    )
    (net (code "55") (name "unconnected-(SW1-Pad2)") (class "Default")
      (node (ref "SW1") (pin "2") (pinfunction "2_2") (pintype "unspecified+no_connect"))
    )
    (net (code "56") (name "unconnected-(SW1-Pad4)") (class "Default")
      (node (ref "SW1") (pin "4") (pinfunction "4_4") (pintype "unspecified+no_connect"))
    )
    (net (code "57") (name "unconnected-(SW2-Pad2)") (class "Default")
      (node (ref "SW2") (pin "2") (pinfunction "2_2") (pintype "unspecified+no_connect"))
    )
    (net (code "58") (name "unconnected-(SW2-Pad4)") (class "Default")
      (node (ref "SW2") (pin "4") (pinfunction "4_4") (pintype "unspecified+no_connect"))
    )
    (net (code "59") (name "unconnected-(SW3-Pad2)") (class "Default")
      (node (ref "SW3") (pin "2") (pinfunction "2_2") (pintype "unspecified+no_connect"))
    )
    (net (code "60") (name "unconnected-(SW3-Pad4)") (class "Default")
      (node (ref "SW3") (pin "4") (pinfunction "4_4") (pintype "unspecified+no_connect"))
    )
    (net (code "61") (name "unconnected-(U1-NC-Pad1)") (class "Default")
      (node (ref "U1") (pin "1") (pinfunction "NC_1") (pintype "unspecified+no_connect"))
    )
    (net (code "62") (name "unconnected-(U1-NC-Pad2)") (class "Default")
      (node (ref "U1") (pin "2") (pinfunction "NC_2") (pintype "unspecified+no_connect"))
    )
    (net (code "63") (name "unconnected-(U1-NC-Pad6)") (class "Default")
      (node (ref "U1") (pin "6") (pinfunction "NC_6") (pintype "unspecified+no_connect"))
    )
    (net (code "64") (name "unconnected-(U1-NC-Pad7)") (class "Default")
      (node (ref "U1") (pin "7") (pinfunction "NC_7") (pintype "unspecified+no_connect"))
    )
    (net (code "65") (name "unconnected-(U1-NC-Pad8)") (class "Default")
      (node (ref "U1") (pin "8") (pinfunction "NC_8") (pintype "unspecified+no_connect"))
    )
    (net (code "66") (name "unconnected-(U3-N.C-Pad1)") (class "Default")
      (node (ref "U3") (pin "1") (pinfunction "N.C_1") (pintype "unspecified+no_connect"))
    )
    (net (code "67") (name "unconnected-(U4-N.C-Pad1)") (class "Default")
      (node (ref "U4") (pin "1") (pinfunction "N.C_1") (pintype "unspecified+no_connect"))
    )
    (net (code "68") (name "unconnected-(U5-N.C-Pad1)") (class "Default")
      (node (ref "U5") (pin "1") (pinfunction "N.C_1") (pintype "unspecified+no_connect"))
    )
    (net (code "69") (name "unconnected-(U6-(ADC3{slash}PTCY)PC3-Pad26)") (class "Default")
      (node (ref "U6") (pin "26") (pinfunction "(ADC3/PTCY)PC3_26") (pintype "bidirectional+no_connect"))
    )
    (net (code "70") (name "unconnected-(U6-(MISO1{slash}ADC0{slash}PTCY)PC0-Pad23)") (class "Default")
      (node (ref "U6") (pin "23") (pinfunction "(MISO1/ADC0/PTCY)PC0_23") (pintype "bidirectional+no_connect"))
    )
    (net (code "71") (name "unconnected-(U6-(OC2B{slash}INT1{slash}PTCXY)PD3-Pad1)") (class "Default")
      (node (ref "U6") (pin "1") (pinfunction "(OC2B/INT1/PTCXY)PD3_1") (pintype "bidirectional+no_connect"))
    )
    (net (code "72") (name "unconnected-(U6-(OC3B{slash}OC4B{slash}INT0{slash}PTCXY)PD2-Pad32)") (class "Default")
      (node (ref "U6") (pin "32") (pinfunction "(OC3B/OC4B/INT0/PTCXY)PD2_32") (pintype "bidirectional+no_connect"))
    )
    (net (code "73") (name "unconnected-(U6-(XCK0{slash}T0{slash}PTCXY)PD4-Pad2)") (class "Default")
      (node (ref "U6") (pin "2") (pinfunction "(XCK0/T0/PTCXY)PD4_2") (pintype "bidirectional+no_connect"))
    )
    (net (code "74") (name "unconnected-(U6-PE0(PTCXY{slash}SDA1{slash}ICP4{slash}ACO)-Pad3)") (class "Default")
      (node (ref "U6") (pin "3") (pinfunction "PE0(PTCXY/SDA1/ICP4/ACO)_3") (pintype "bidirectional+no_connect"))
    )
    (net (code "75") (name "unconnected-(U6-PE2(PTCY{slash}ADC6{slash}ICP3{slash}SS1)-Pad19)") (class "Default")
      (node (ref "U6") (pin "19") (pinfunction "PE2(PTCY/ADC6/ICP3/SS1)_19") (pintype "bidirectional+no_connect"))
    )
    (net (code "76") (name "unconnected-(U6-PE3(PTCY{slash}ADC7{slash}T3{slash}MOSI1)-Pad22)") (class "Default")
      (node (ref "U6") (pin "22") (pinfunction "PE3(PTCY/ADC7/T3/MOSI1)_22") (pintype "bidirectional+no_connect"))
    )
  )
)
